# controllerBox.net
KiCad netlist of a schematic drawn in EAGLE
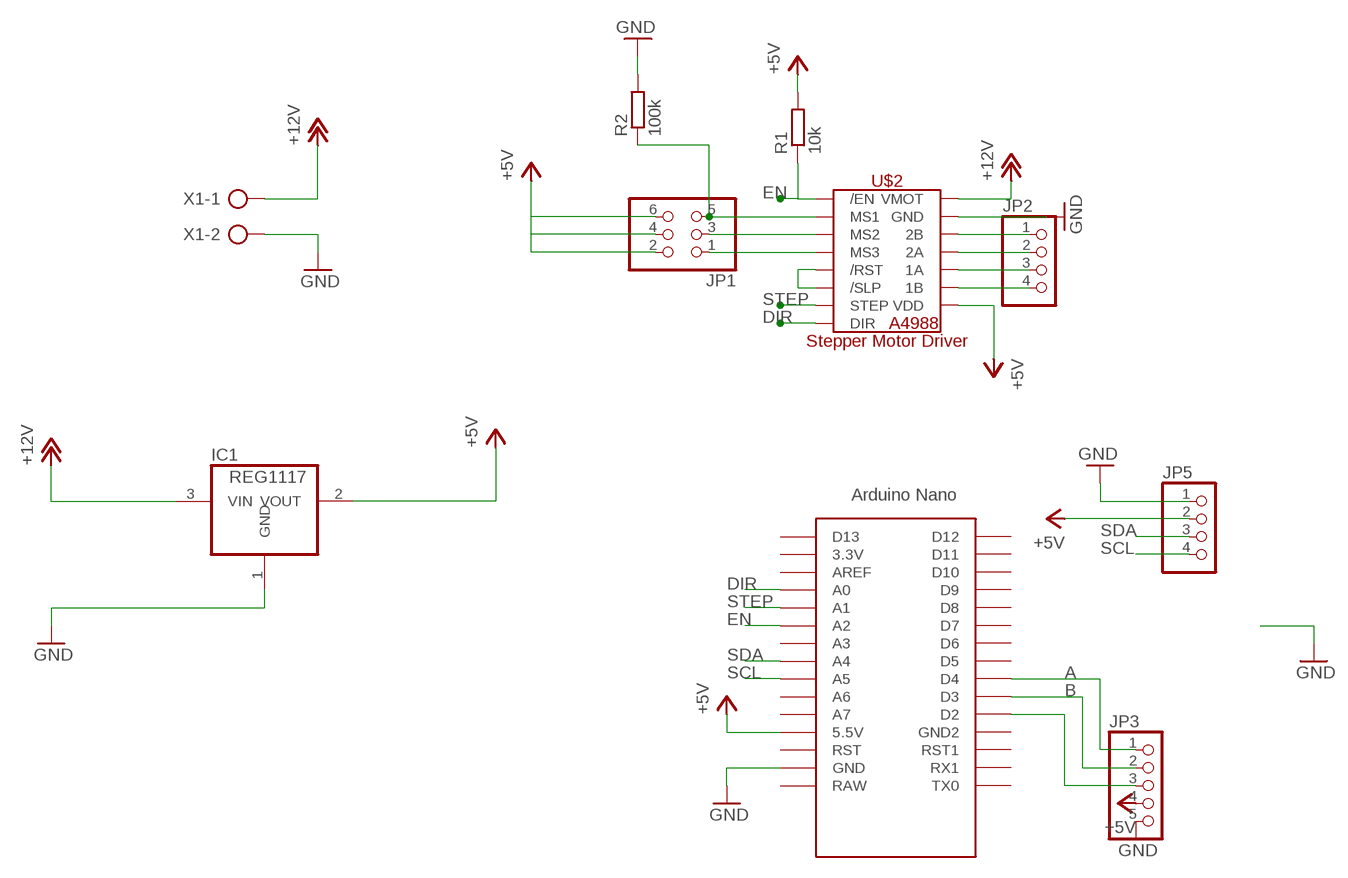
[diagram p0: schematic, sheet 1]

(export (version "E")
  (design (tool "Eeschema 10.0.6"))
  (components
    (comp (ref "IC1")
      (value "REG1117")
      (footprint "eagle-import:SOT223")
      (libsource (lib "eagle-import") (part "REG1117"))
    )
    (comp (ref "JP1")
      (value "PINHD-2X3")
      (footprint "eagle-import:2X03")
      (libsource (lib "eagle-import") (part "PINHD-2X3"))
    )
    (comp (ref "JP2")
      (value "PINHD-1X4")
      (footprint "eagle-import:1X04")
      (libsource (lib "eagle-import") (part "PINHD-1X4"))
    )
    (comp (ref "JP3")
      (value "PINHD-1X5")
      (footprint "eagle-import:1X05")
      (libsource (lib "eagle-import") (part "PINHD-1X5"))
    )
    (comp (ref "JP5")
      (value "PINHD-1X4")
      (footprint "eagle-import:1X04")
      (libsource (lib "eagle-import") (part "PINHD-1X4"))
    )
    (comp (ref "R1")
      (value "10k")
      (footprint "eagle-import:0207_10")
      (libsource (lib "eagle-import") (part "R-EU_0207/10"))
    )
    (comp (ref "R2")
      (value "100k")
      (footprint "eagle-import:0207_10")
      (libsource (lib "eagle-import") (part "R-EU_0207/10"))
    )
    (comp (ref "U$1")
      (value "NANO")
      (footprint "eagle-import:NANO")
      (libsource (lib "eagle-import") (part "NANO"))
    )
    (comp (ref "U$2")
      (value "A4988_STEP")
      (footprint "eagle-import:A4988_STEP")
      (libsource (lib "eagle-import") (part "A4988_STEP"))
    )
    (comp (ref "X1")
      (value "AK300/2")
      (footprint "eagle-import:AK300_2")
      (libsource (lib "eagle-import") (part "AK300/2"))
    )
  )
  (nets
    (net (code "1") (name "+5V") (class "Default")
      (node (ref "IC1") (pin "2") (pinfunction "VOUT_2") (pintype "output"))
      (node (ref "JP1") (pin "2") (pinfunction "2_2") (pintype "passive"))
      (node (ref "JP1") (pin "4") (pinfunction "4_4") (pintype "passive"))
      (node (ref "JP1") (pin "6") (pinfunction "6_6") (pintype "passive"))
      (node (ref "JP3") (pin "4") (pinfunction "4_4") (pintype "passive"))
      (node (ref "JP5") (pin "2") (pinfunction "2_2") (pintype "passive"))
      (node (ref "R1") (pin "2") (pinfunction "2_2") (pintype "passive"))
      (node (ref "U$1") (pin "5V") (pinfunction "5.5V_5V") (pintype "bidirectional"))
      (node (ref "U$2") (pin "VDD") (pinfunction "VDD_VDD") (pintype "bidirectional"))
    )
    (net (code "2") (name "+12V") (class "Default")
      (node (ref "IC1") (pin "3") (pinfunction "VIN_3") (pintype "input"))
      (node (ref "U$2") (pin "VMOT") (pinfunction "VMOT_VMOT") (pintype "bidirectional"))
      (node (ref "X1") (pin "1") (pinfunction "KL_1") (pintype "passive"))
    )
    (net (code "3") (name "/A") (class "Default")
      (node (ref "JP3") (pin "1") (pinfunction "1_1") (pintype "passive"))
      (node (ref "U$1") (pin "D4") (pinfunction "D4_D4") (pintype "bidirectional"))
    )
    (net (code "4") (name "/B") (class "Default")
      (node (ref "JP3") (pin "2") (pinfunction "2_2") (pintype "passive"))
      (node (ref "U$1") (pin "D3") (pinfunction "D3_D3") (pintype "bidirectional"))
    )
    (net (code "5") (name "/DIR") (class "Default")
      (node (ref "U$1") (pin "A0") (pinfunction "A0_A0") (pintype "bidirectional"))
      (node (ref "U$2") (pin "DIR") (pinfunction "DIR_DIR") (pintype "bidirectional"))
    )
    (net (code "6") (name "/EN") (class "Default")
      (node (ref "R1") (pin "1") (pinfunction "1_1") (pintype "passive"))
      (node (ref "U$1") (pin "A2") (pinfunction "A2_A2") (pintype "bidirectional"))
      (node (ref "U$2") (pin "/EN") (pinfunction "/EN_/EN") (pintype "bidirectional"))
    )
    (net (code "7") (name "/SCL") (class "Default")
      (node (ref "JP5") (pin "4") (pinfunction "4_4") (pintype "passive"))
      (node (ref "U$1") (pin "A5") (pinfunction "A5_A5") (pintype "bidirectional"))
    )
    (net (code "8") (name "/SDA") (class "Default")
      (node (ref "JP5") (pin "3") (pinfunction "3_3") (pintype "passive"))
      (node (ref "U$1") (pin "A4") (pinfunction "A4_A4") (pintype "bidirectional"))
    )
    (net (code "9") (name "/STEP") (class "Default")
      (node (ref "U$1") (pin "A1") (pinfunction "A1_A1") (pintype "bidirectional"))
      (node (ref "U$2") (pin "STEP") (pinfunction "STEP_STEP") (pintype "bidirectional"))
    )
    (net (code "10") (name "GND") (class "Default")
      (node (ref "IC1") (pin "1") (pinfunction "GND_1") (pintype "power_in"))
      (node (ref "JP3") (pin "5") (pinfunction "5_5") (pintype "passive"))
      (node (ref "JP5") (pin "1") (pinfunction "1_1") (pintype "passive"))
      (node (ref "R2") (pin "2") (pinfunction "2_2") (pintype "passive"))
      (node (ref "U$1") (pin "GND") (pinfunction "GND_GND") (pintype "bidirectional"))
      (node (ref "U$2") (pin "GND") (pinfunction "GND_GND") (pintype "bidirectional"))
      (node (ref "U$2") (pin "GND2") (pinfunction "GND_GND2") (pintype "bidirectional"))
      (node (ref "X1") (pin "2") (pinfunction "KL_2") (pintype "passive"))
    )
    (net (code "11") (name "Net-(JP1-Pad1)") (class "Default")
      (node (ref "JP1") (pin "1") (pinfunction "1_1") (pintype "passive"))
      (node (ref "U$2") (pin "MS3") (pinfunction "MS3_MS3") (pintype "bidirectional"))
    )
    (net (code "12") (name "Net-(JP1-Pad3)") (class "Default")
      (node (ref "JP1") (pin "3") (pinfunction "3_3") (pintype "passive"))
      (node (ref "U$2") (pin "MS2") (pinfunction "MS2_MS2") (pintype "bidirectional"))
    )
    (net (code "13") (name "Net-(JP1-Pad5)") (class "Default")
      (node (ref "JP1") (pin "5") (pinfunction "5_5") (pintype "passive"))
      (node (ref "R2") (pin "1") (pinfunction "1_1") (pintype "passive"))
      (node (ref "U$2") (pin "MS1") (pinfunction "MS1_MS1") (pintype "bidirectional"))
    )
    (net (code "14") (name "Net-(JP2-Pad1)") (class "Default")
      (node (ref "JP2") (pin "1") (pinfunction "1_1") (pintype "passive"))
      (node (ref "U$2") (pin "2B") (pinfunction "2B_2B") (pintype "bidirectional"))
    )
    (net (code "15") (name "Net-(JP2-Pad2)") (class "Default")
      (node (ref "JP2") (pin "2") (pinfunction "2_2") (pintype "passive"))
      (node (ref "U$2") (pin "2A") (pinfunction "2A_2A") (pintype "bidirectional"))
    )
    (net (code "16") (name "Net-(JP2-Pad3)") (class "Default")
      (node (ref "JP2") (pin "3") (pinfunction "3_3") (pintype "passive"))
      (node (ref "U$2") (pin "1A") (pinfunction "1A_1A") (pintype "bidirectional"))
    )
    (net (code "17") (name "Net-(JP2-Pad4)") (class "Default")
      (node (ref "JP2") (pin "4") (pinfunction "4_4") (pintype "passive"))
      (node (ref "U$2") (pin "1B") (pinfunction "1B_1B") (pintype "bidirectional"))
    )
    (net (code "18") (name "Net-(JP3-Pad3)") (class "Default")
      (node (ref "JP3") (pin "3") (pinfunction "3_3") (pintype "passive"))
      (node (ref "U$1") (pin "D2") (pinfunction "D2_D2") (pintype "bidirectional"))
    )
    (net (code "19") (name "Net-(U$2-Pad{slash}RST)") (class "Default")
      (node (ref "U$2") (pin "/RST") (pinfunction "/RST_/RST") (pintype "bidirectional"))
      (node (ref "U$2") (pin "/SLP") (pinfunction "/SLP_/SLP") (pintype "bidirectional"))
    )
    (net (code "20") (name "unconnected-(U$1-GND2-PadGND1)") (class "Default")
      (node (ref "U$1") (pin "GND1") (pinfunction "GND2_GND1") (pintype "bidirectional"))
    )
    (net (code "21") (name "unconnected-(U$1-Pad3.3V)") (class "Default")
      (node (ref "U$1") (pin "3.3V") (pinfunction "3.3V_3.3V") (pintype "bidirectional"))
    )
    (net (code "22") (name "unconnected-(U$1-PadA3)") (class "Default")
      (node (ref "U$1") (pin "A3") (pinfunction "A3_A3") (pintype "bidirectional"))
    )
    (net (code "23") (name "unconnected-(U$1-PadA6)") (class "Default")
      (node (ref "U$1") (pin "A6") (pinfunction "A6_A6") (pintype "bidirectional"))
    )
    (net (code "24") (name "unconnected-(U$1-PadA7)") (class "Default")
      (node (ref "U$1") (pin "A7") (pinfunction "A7_A7") (pintype "bidirectional"))
    )
    (net (code "25") (name "unconnected-(U$1-PadAREF)") (class "Default")
      (node (ref "U$1") (pin "AREF") (pinfunction "AREF_AREF") (pintype "bidirectional"))
    )
    (net (code "26") (name "unconnected-(U$1-PadD5)") (class "Default")
      (node (ref "U$1") (pin "D5") (pinfunction "D5_D5") (pintype "bidirectional"))
    )
    (net (code "27") (name "unconnected-(U$1-PadD6)") (class "Default")
      (node (ref "U$1") (pin "D6") (pinfunction "D6_D6") (pintype "bidirectional"))
    )
    (net (code "28") (name "unconnected-(U$1-PadD7)") (class "Default")
      (node (ref "U$1") (pin "D7") (pinfunction "D7_D7") (pintype "bidirectional"))
    )
    (net (code "29") (name "unconnected-(U$1-PadD8)") (class "Default")
      (node (ref "U$1") (pin "D8") (pinfunction "D8_D8") (pintype "bidirectional"))
    )
    (net (code "30") (name "unconnected-(U$1-PadD9)") (class "Default")
      (node (ref "U$1") (pin "D9") (pinfunction "D9_D9") (pintype "bidirectional"))
    )
    (net (code "31") (name "unconnected-(U$1-PadD10)") (class "Default")
      (node (ref "U$1") (pin "D10") (pinfunction "D10_D10") (pintype "bidirectional"))
    )
    (net (code "32") (name "unconnected-(U$1-PadD11)") (class "Default")
      (node (ref "U$1") (pin "D11") (pinfunction "D11_D11") (pintype "bidirectional"))
    )
    (net (code "33") (name "unconnected-(U$1-PadD12)") (class "Default")
      (node (ref "U$1") (pin "D12") (pinfunction "D12_D12") (pintype "bidirectional"))
    )
    (net (code "34") (name "unconnected-(U$1-PadD13)") (class "Default")
      (node (ref "U$1") (pin "D13") (pinfunction "D13_D13") (pintype "bidirectional"))
    )
    (net (code "35") (name "unconnected-(U$1-PadICSP1)") (class "Default")
      (node (ref "U$1") (pin "ICSP1") (pinfunction "ICSP1_ICSP1") (pintype "bidirectional"))
    )
    (net (code "36") (name "unconnected-(U$1-PadICSP2)") (class "Default")
      (node (ref "U$1") (pin "ICSP2") (pinfunction "ICSP2_ICSP2") (pintype "bidirectional"))
    )
    (net (code "37") (name "unconnected-(U$1-PadICSP3)") (class "Default")
      (node (ref "U$1") (pin "ICSP3") (pinfunction "ICSP3_ICSP3") (pintype "bidirectional"))
    )
    (net (code "38") (name "unconnected-(U$1-PadICSP4)") (class "Default")
      (node (ref "U$1") (pin "ICSP4") (pinfunction "ICSP4_ICSP4") (pintype "bidirectional"))
    )
    (net (code "39") (name "unconnected-(U$1-PadICSP5)") (class "Default")
      (node (ref "U$1") (pin "ICSP5") (pinfunction "ICSP5_ICSP5") (pintype "bidirectional"))
    )
    (net (code "40") (name "unconnected-(U$1-PadICSP6)") (class "Default")
      (node (ref "U$1") (pin "ICSP6") (pinfunction "ICSP6_ICSP6") (pintype "bidirectional"))
    )
    (net (code "41") (name "unconnected-(U$1-PadRAW)") (class "Default")
      (node (ref "U$1") (pin "RAW") (pinfunction "RAW_RAW") (pintype "bidirectional"))
    )
    (net (code "42") (name "unconnected-(U$1-PadRST)") (class "Default")
      (node (ref "U$1") (pin "RST") (pinfunction "RST_RST") (pintype "bidirectional"))
    )
    (net (code "43") (name "unconnected-(U$1-PadRST1)") (class "Default")
      (node (ref "U$1") (pin "RST1") (pinfunction "RST1_RST1") (pintype "bidirectional"))
    )
    (net (code "44") (name "unconnected-(U$1-PadRX1)") (class "Default")
      (node (ref "U$1") (pin "RX1") (pinfunction "RX1_RX1") (pintype "bidirectional"))
    )
    (net (code "45") (name "unconnected-(U$1-PadTX0)") (class "Default")
      (node (ref "U$1") (pin "TX0") (pinfunction "TX0_TX0") (pintype "bidirectional"))
    )
  )
)
